# obdlogger_v0_2.net
KiCad netlist of a schematic drawn in EAGLE
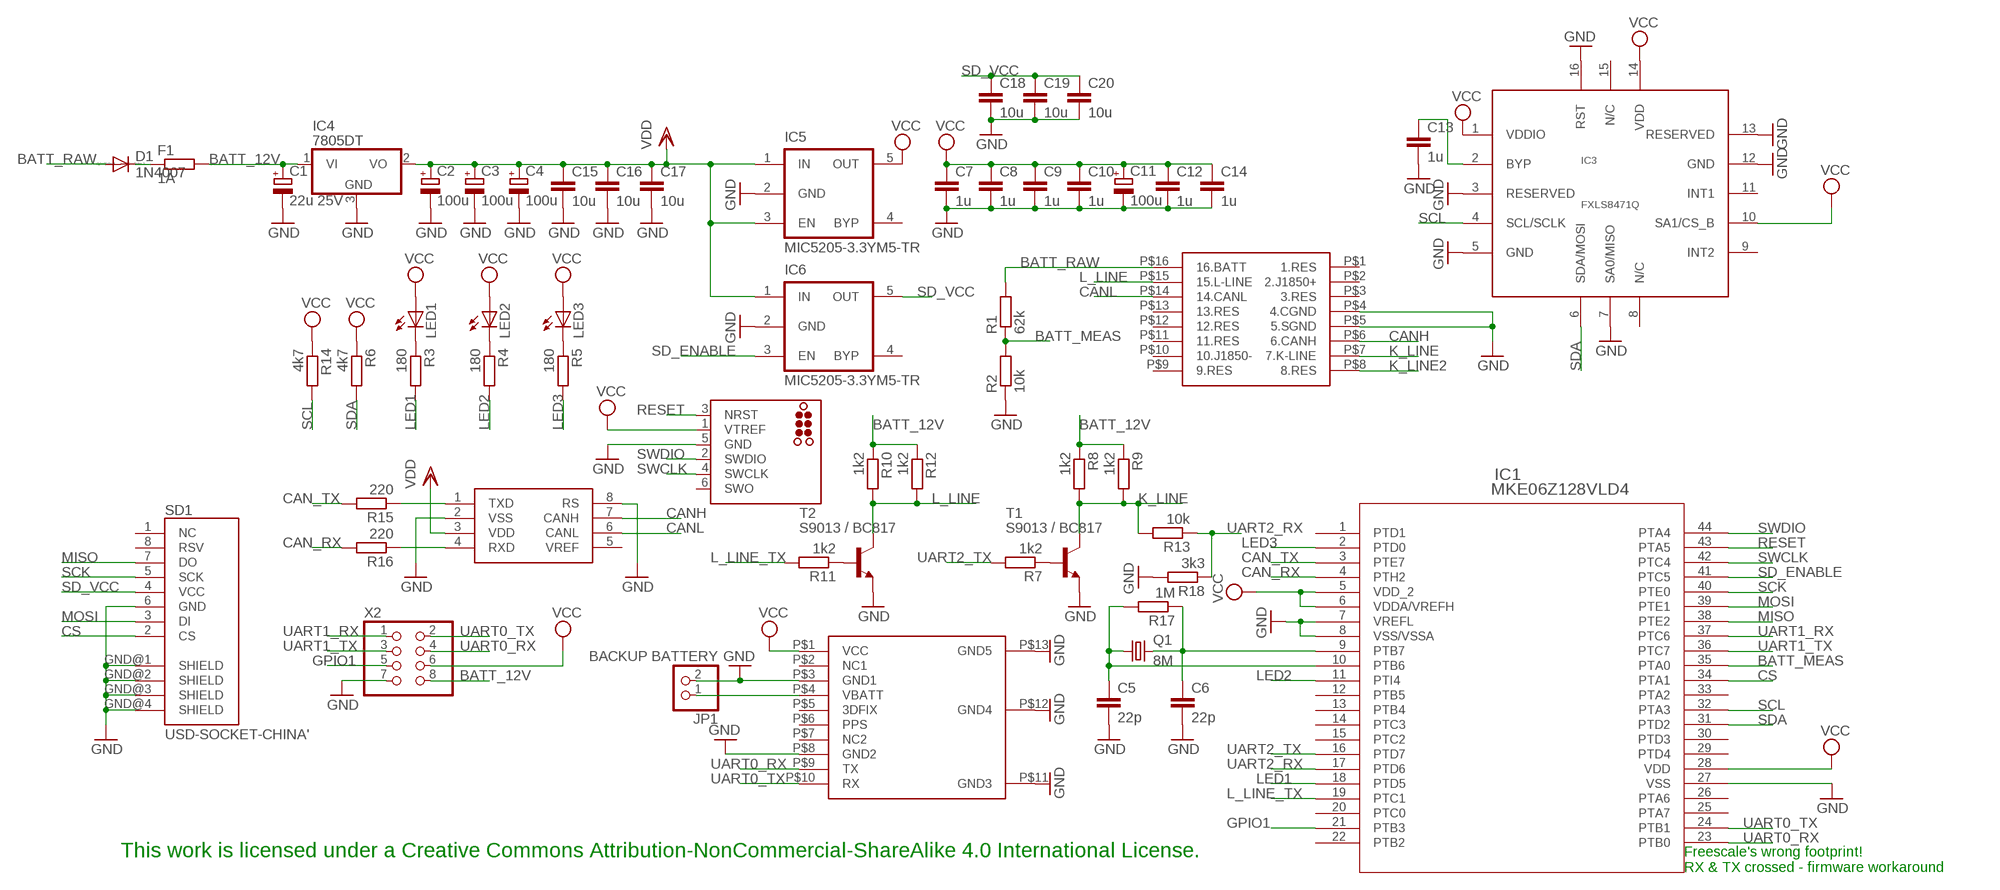
[diagram p0: schematic, sheet 1]

(export (version "E")
  (design (tool "Eeschema 10.0.6"))
  (components
    (comp (ref "C1")
      (value "22u 25V")
      (footprint "eagle-import:SMC_C")
      (libsource (lib "eagle-import") (part "CPOL-EUSMCC"))
    )
    (comp (ref "C2")
      (value "100u")
      (footprint "eagle-import:SMC_B")
      (libsource (lib "eagle-import") (part "CPOL-EUSMCB"))
    )
    (comp (ref "C3")
      (value "100u")
      (footprint "eagle-import:SMC_B")
      (libsource (lib "eagle-import") (part "CPOL-EUSMCB"))
    )
    (comp (ref "C4")
      (value "100u")
      (footprint "eagle-import:SMC_B")
      (libsource (lib "eagle-import") (part "CPOL-EUSMCB"))
    )
    (comp (ref "C5")
      (value "22p")
      (footprint "eagle-import:C0603K")
      (libsource (lib "eagle-import") (part "C-EUC0603K"))
    )
    (comp (ref "C6")
      (value "22p")
      (footprint "eagle-import:C0603K")
      (libsource (lib "eagle-import") (part "C-EUC0603K"))
    )
    (comp (ref "C7")
      (value "1u")
      (footprint "eagle-import:C0603K")
      (libsource (lib "eagle-import") (part "C-EUC0603K"))
    )
    (comp (ref "C8")
      (value "1u")
      (footprint "eagle-import:C0603K")
      (libsource (lib "eagle-import") (part "C-EUC0603K"))
    )
    (comp (ref "C9")
      (value "1u")
      (footprint "eagle-import:C0603K")
      (libsource (lib "eagle-import") (part "C-EUC0603K"))
    )
    (comp (ref "C10")
      (value "1u")
      (footprint "eagle-import:C0603K")
      (libsource (lib "eagle-import") (part "C-EUC0603K"))
    )
    (comp (ref "C11")
      (value "100u")
      (footprint "eagle-import:SMC_B")
      (libsource (lib "eagle-import") (part "CPOL-EUSMCB"))
    )
    (comp (ref "C12")
      (value "1u")
      (footprint "eagle-import:C0603K")
      (libsource (lib "eagle-import") (part "C-EUC0603K"))
    )
    (comp (ref "C13")
      (value "1u")
      (footprint "eagle-import:C0603K")
      (libsource (lib "eagle-import") (part "C-EUC0603K"))
    )
    (comp (ref "C14")
      (value "1u")
      (footprint "eagle-import:C0603K")
      (libsource (lib "eagle-import") (part "C-EUC0603K"))
    )
    (comp (ref "C15")
      (value "10u")
      (footprint "eagle-import:C0603K")
      (libsource (lib "eagle-import") (part "C-EUC0603K"))
    )
    (comp (ref "C16")
      (value "10u")
      (footprint "eagle-import:C0603K")
      (libsource (lib "eagle-import") (part "C-EUC0603K"))
    )
    (comp (ref "C17")
      (value "10u")
      (footprint "eagle-import:C0603K")
      (libsource (lib "eagle-import") (part "C-EUC0603K"))
    )
    (comp (ref "C18")
      (value "10u")
      (footprint "eagle-import:C0603K")
      (libsource (lib "eagle-import") (part "C-EUC0603K"))
    )
    (comp (ref "C19")
      (value "10u")
      (footprint "eagle-import:C0603K")
      (libsource (lib "eagle-import") (part "C-EUC0603K"))
    )
    (comp (ref "C20")
      (value "10u")
      (footprint "eagle-import:C0603K")
      (libsource (lib "eagle-import") (part "C-EUC0603K"))
    )
    (comp (ref "D1")
      (value "1N4007")
      (footprint "eagle-import:C1702-05")
      (libsource (lib "eagle-import") (part "DIODE-C1702-05"))
    )
    (comp (ref "F1")
      (value "1A")
      (footprint "eagle-import:R1206")
      (libsource (lib "eagle-import") (part "resistor_348_R-EU_R1206"))
    )
    (comp (ref "IC1")
      (value "MKE06Z128VLD4")
      (footprint "eagle-import:LQFP-44_10X10X1.4")
      (fields (field (name "MANUFACTURER_PART_NUMBER") "mke06z128vld4"))
      (libsource (lib "eagle-import") (part "MKE06Z128VLD4"))
    )
    (comp (ref "IC2")
      (value "MCP2561")
      (footprint "eagle-import:SO08")
      (libsource (lib "eagle-import") (part "MCP2551"))
    )
    (comp (ref "IC3")
      (value "FXLS8471Q")
      (footprint "eagle-import:16QFN-5_3")
      (libsource (lib "eagle-import") (part "FXLS8471Q"))
    )
    (comp (ref "IC4")
      (value "7805DT")
      (footprint "eagle-import:TO252")
      (libsource (lib "eagle-import") (part "78DT05"))
    )
    (comp (ref "IC5")
      (value "MIC5205-3.3YM5-TR")
      (footprint "eagle-import:SOT-23-5")
      (libsource (lib "eagle-import") (part "MIC5205"))
    )
    (comp (ref "IC6")
      (value "MIC5205-3.3YM5-TR")
      (footprint "eagle-import:SOT-23-5")
      (libsource (lib "eagle-import") (part "MIC5205"))
    )
    (comp (ref "JP1")
      (value "BACKUP BATTERY")
      (footprint "eagle-import:1X02")
      (libsource (lib "eagle-import") (part "PINHD-1X2"))
    )
    (comp (ref "LED1")
      (value "LED3MM")
      (footprint "eagle-import:LED3MM")
      (libsource (lib "eagle-import") (part "LED3MM"))
    )
    (comp (ref "LED2")
      (value "LED3MM")
      (footprint "eagle-import:LED3MM")
      (libsource (lib "eagle-import") (part "LED3MM"))
    )
    (comp (ref "LED3")
      (value "LED3MM")
      (footprint "eagle-import:LED3MM")
      (libsource (lib "eagle-import") (part "LED3MM"))
    )
    (comp (ref "Q1")
      (value "8M")
      (footprint "eagle-import:HC49UP")
      (libsource (lib "eagle-import") (part "CRYSTALHC49UP"))
    )
    (comp (ref "R1")
      (value "62k")
      (footprint "eagle-import:R0603")
      (libsource (lib "eagle-import") (part "R-EU_R0603"))
    )
    (comp (ref "R2")
      (value "10k")
      (footprint "eagle-import:R0603")
      (libsource (lib "eagle-import") (part "R-EU_R0603"))
    )
    (comp (ref "R3")
      (value "180")
      (footprint "eagle-import:R0603")
      (libsource (lib "eagle-import") (part "R-EU_R0603"))
    )
    (comp (ref "R4")
      (value "180")
      (footprint "eagle-import:R0603")
      (libsource (lib "eagle-import") (part "R-EU_R0603"))
    )
    (comp (ref "R5")
      (value "180")
      (footprint "eagle-import:R0603")
      (libsource (lib "eagle-import") (part "R-EU_R0603"))
    )
    (comp (ref "R6")
      (value "4k7")
      (footprint "eagle-import:R0603")
      (libsource (lib "eagle-import") (part "R-EU_R0603"))
    )
    (comp (ref "R7")
      (value "1k2")
      (footprint "eagle-import:R0603")
      (libsource (lib "eagle-import") (part "R-EU_R0603"))
    )
    (comp (ref "R8")
      (value "1k2")
      (footprint "eagle-import:M1206")
      (libsource (lib "eagle-import") (part "R-EU_M1206"))
    )
    (comp (ref "R9")
      (value "1k2")
      (footprint "eagle-import:M1206")
      (libsource (lib "eagle-import") (part "R-EU_M1206"))
    )
    (comp (ref "R10")
      (value "1k2")
      (footprint "eagle-import:M1206")
      (libsource (lib "eagle-import") (part "R-EU_M1206"))
    )
    (comp (ref "R11")
      (value "1k2")
      (footprint "eagle-import:R0603")
      (libsource (lib "eagle-import") (part "R-EU_R0603"))
    )
    (comp (ref "R12")
      (value "1k2")
      (footprint "eagle-import:M1206")
      (libsource (lib "eagle-import") (part "R-EU_M1206"))
    )
    (comp (ref "R13")
      (value "10k")
      (footprint "eagle-import:R0603")
      (libsource (lib "eagle-import") (part "R-EU_R0603"))
    )
    (comp (ref "R14")
      (value "4k7")
      (footprint "eagle-import:R0603")
      (libsource (lib "eagle-import") (part "R-EU_R0603"))
    )
    (comp (ref "R15")
      (value "220")
      (footprint "eagle-import:R0603")
      (libsource (lib "eagle-import") (part "R-EU_R0603"))
    )
    (comp (ref "R16")
      (value "220")
      (footprint "eagle-import:R0603")
      (libsource (lib "eagle-import") (part "R-EU_R0603"))
    )
    (comp (ref "R17")
      (value "1M")
      (footprint "eagle-import:R0603")
      (libsource (lib "eagle-import") (part "R-EU_R0603"))
    )
    (comp (ref "R18")
      (value "3k3")
      (footprint "eagle-import:R0603")
      (libsource (lib "eagle-import") (part "R-EU_R0603"))
    )
    (comp (ref "SD1")
      (value "USD-SOCKET-CHINA'")
      (footprint "eagle-import:USD-SOCKET-PP")
      (libsource (lib "eagle-import") (part "USD-SOCKET-CHINA'"))
    )
    (comp (ref "T1")
      (value "S9013 / BC817")
      (footprint "eagle-import:SOT23-BEC")
      (libsource (lib "eagle-import") (part "-NPN-SOT23-BECBC817-16"))
    )
    (comp (ref "T2")
      (value "S9013 / BC817")
      (footprint "eagle-import:SOT23-BEC")
      (libsource (lib "eagle-import") (part "-NPN-SOT23-BECBC817-16"))
    )
    (comp (ref "U$2")
      (value "SWD-NEEDLE")
      (footprint "eagle-import:TC2030-MCP")
      (libsource (lib "eagle-import") (part "SWD-NEEDLE"))
    )
    (comp (ref "U$4")
      (value "PA6C")
      (footprint "eagle-import:PA6C")
      (libsource (lib "eagle-import") (part "PA6C"))
    )
    (comp (ref "X1")
      (value "OBD2-RIGHT-ANGLEPROPER")
      (footprint "eagle-import:OBD2-RIGHT-ANGLE-PCB-PROPER")
      (libsource (lib "eagle-import") (part "OBD2-RIGHT-ANGLEPROPER"))
    )
    (comp (ref "X2")
      (value "PINHD-2X4")
      (footprint "eagle-import:2X04")
      (libsource (lib "eagle-import") (part "PINHD-2X4"))
    )
  )
  (nets
    (net (code "1") (name "/BATT_12V") (class "Default")
      (node (ref "C1") (pin "+") (pinfunction "+_+") (pintype "passive"))
      (node (ref "F1") (pin "2") (pinfunction "2_2") (pintype "passive"))
      (node (ref "IC4") (pin "1") (pinfunction "VI_1") (pintype "input"))
      (node (ref "R10") (pin "1") (pinfunction "1_1") (pintype "passive"))
      (node (ref "R12") (pin "1") (pinfunction "1_1") (pintype "passive"))
      (node (ref "R8") (pin "1") (pinfunction "1_1") (pintype "passive"))
      (node (ref "R9") (pin "1") (pinfunction "1_1") (pintype "passive"))
      (node (ref "X2") (pin "8") (pinfunction "8_8") (pintype "passive"))
    )
    (net (code "2") (name "/BATT_MEAS") (class "Default")
      (node (ref "IC1") (pin "35") (pinfunction "PTA0_35") (pintype "bidirectional"))
      (node (ref "R1") (pin "1") (pinfunction "1_1") (pintype "passive"))
      (node (ref "R2") (pin "2") (pinfunction "2_2") (pintype "passive"))
    )
    (net (code "3") (name "/BATT_RAW") (class "Default")
      (node (ref "D1") (pin "A") (pinfunction "A_A") (pintype "passive"))
      (node (ref "R1") (pin "2") (pinfunction "2_2") (pintype "passive"))
      (node (ref "X1") (pin "P$16") (pinfunction "16.BATT_P$16") (pintype "bidirectional"))
    )
    (net (code "4") (name "/CANH") (class "Default")
      (node (ref "IC2") (pin "7") (pinfunction "CANH_7") (pintype "bidirectional"))
      (node (ref "X1") (pin "P$6") (pinfunction "6.CANH_P$6") (pintype "bidirectional"))
    )
    (net (code "5") (name "/CANL") (class "Default")
      (node (ref "IC2") (pin "6") (pinfunction "CANL_6") (pintype "bidirectional"))
      (node (ref "X1") (pin "P$14") (pinfunction "14.CANL_P$14") (pintype "bidirectional"))
    )
    (net (code "6") (name "/CAN_RX") (class "Default")
      (node (ref "IC1") (pin "4") (pinfunction "PTH2_4") (pintype "bidirectional"))
      (node (ref "R16") (pin "2") (pinfunction "2_2") (pintype "passive"))
    )
    (net (code "7") (name "/CAN_TX") (class "Default")
      (node (ref "IC1") (pin "3") (pinfunction "PTE7_3") (pintype "bidirectional"))
      (node (ref "R15") (pin "2") (pinfunction "2_2") (pintype "passive"))
    )
    (net (code "8") (name "/CS") (class "Default")
      (node (ref "IC1") (pin "34") (pinfunction "PTA1_34") (pintype "bidirectional"))
      (node (ref "SD1") (pin "2") (pinfunction "CS_2") (pintype "bidirectional"))
    )
    (net (code "9") (name "/GPIO1") (class "Default")
      (node (ref "IC1") (pin "21") (pinfunction "PTB3_21") (pintype "bidirectional"))
      (node (ref "X2") (pin "5") (pinfunction "5_5") (pintype "passive"))
    )
    (net (code "10") (name "/K_LINE") (class "Default")
      (node (ref "R13") (pin "2") (pinfunction "2_2") (pintype "passive"))
      (node (ref "R8") (pin "2") (pinfunction "2_2") (pintype "passive"))
      (node (ref "R9") (pin "2") (pinfunction "2_2") (pintype "passive"))
      (node (ref "T1") (pin "C") (pinfunction "C_C") (pintype "passive"))
      (node (ref "X1") (pin "P$7") (pinfunction "7.K-LINE_P$7") (pintype "bidirectional"))
    )
    (net (code "11") (name "/K_LINE2") (class "Default")
      (node (ref "X1") (pin "P$8") (pinfunction "8.RES_P$8") (pintype "bidirectional"))
    )
    (net (code "12") (name "/LED1") (class "Default")
      (node (ref "IC1") (pin "18") (pinfunction "PTD5_18") (pintype "bidirectional"))
      (node (ref "R3") (pin "2") (pinfunction "2_2") (pintype "passive"))
    )
    (net (code "13") (name "/LED2") (class "Default")
      (node (ref "IC1") (pin "11") (pinfunction "PTI4_11") (pintype "bidirectional"))
      (node (ref "R4") (pin "2") (pinfunction "2_2") (pintype "passive"))
    )
    (net (code "14") (name "/LED3") (class "Default")
      (node (ref "IC1") (pin "2") (pinfunction "PTD0_2") (pintype "bidirectional"))
      (node (ref "R5") (pin "2") (pinfunction "2_2") (pintype "passive"))
    )
    (net (code "15") (name "/L_LINE") (class "Default")
      (node (ref "R10") (pin "2") (pinfunction "2_2") (pintype "passive"))
      (node (ref "R12") (pin "2") (pinfunction "2_2") (pintype "passive"))
      (node (ref "T2") (pin "C") (pinfunction "C_C") (pintype "passive"))
      (node (ref "X1") (pin "P$15") (pinfunction "15.L-LINE_P$15") (pintype "bidirectional"))
    )
    (net (code "16") (name "/L_LINE_TX") (class "Default")
      (node (ref "IC1") (pin "19") (pinfunction "PTC1_19") (pintype "bidirectional"))
      (node (ref "R11") (pin "2") (pinfunction "2_2") (pintype "passive"))
    )
    (net (code "17") (name "/MISO") (class "Default")
      (node (ref "IC1") (pin "38") (pinfunction "PTE2_38") (pintype "bidirectional"))
      (node (ref "SD1") (pin "7") (pinfunction "DO_7") (pintype "bidirectional"))
    )
    (net (code "18") (name "/MOSI") (class "Default")
      (node (ref "IC1") (pin "39") (pinfunction "PTE1_39") (pintype "bidirectional"))
      (node (ref "SD1") (pin "3") (pinfunction "DI_3") (pintype "bidirectional"))
    )
    (net (code "19") (name "/RESET") (class "Default")
      (node (ref "IC1") (pin "43") (pinfunction "PTA5_43") (pintype "bidirectional"))
      (node (ref "U$2") (pin "3") (pinfunction "NRST_3") (pintype "passive"))
    )
    (net (code "20") (name "/SCK") (class "Default")
      (node (ref "IC1") (pin "40") (pinfunction "PTE0_40") (pintype "bidirectional"))
      (node (ref "SD1") (pin "5") (pinfunction "SCK_5") (pintype "bidirectional"))
    )
    (net (code "21") (name "/SCL") (class "Default")
      (node (ref "IC1") (pin "32") (pinfunction "PTA3_32") (pintype "bidirectional"))
      (node (ref "IC3") (pin "4") (pinfunction "SCL/SCLK_4") (pintype "bidirectional"))
      (node (ref "R14") (pin "2") (pinfunction "2_2") (pintype "passive"))
    )
    (net (code "22") (name "/SDA") (class "Default")
      (node (ref "IC1") (pin "31") (pinfunction "PTD2_31") (pintype "bidirectional"))
      (node (ref "IC3") (pin "6") (pinfunction "SDA/MOSI_6") (pintype "bidirectional"))
      (node (ref "R6") (pin "2") (pinfunction "2_2") (pintype "passive"))
    )
    (net (code "23") (name "/SD_ENABLE") (class "Default")
      (node (ref "IC1") (pin "41") (pinfunction "PTC5_41") (pintype "bidirectional"))
      (node (ref "IC6") (pin "3") (pinfunction "EN_3") (pintype "bidirectional"))
    )
    (net (code "24") (name "/SD_VCC") (class "Default")
      (node (ref "C18") (pin "1") (pinfunction "1_1") (pintype "passive"))
      (node (ref "C19") (pin "1") (pinfunction "1_1") (pintype "passive"))
      (node (ref "C20") (pin "1") (pinfunction "1_1") (pintype "passive"))
      (node (ref "IC6") (pin "5") (pinfunction "OUT_5") (pintype "bidirectional"))
      (node (ref "SD1") (pin "4") (pinfunction "VCC_4") (pintype "bidirectional"))
    )
    (net (code "25") (name "/SWCLK") (class "Default")
      (node (ref "IC1") (pin "42") (pinfunction "PTC4_42") (pintype "bidirectional"))
      (node (ref "U$2") (pin "4") (pinfunction "SWCLK_4") (pintype "output"))
    )
    (net (code "26") (name "/SWDIO") (class "Default")
      (node (ref "IC1") (pin "44") (pinfunction "PTA4_44") (pintype "bidirectional"))
      (node (ref "U$2") (pin "2") (pinfunction "SWDIO_2") (pintype "bidirectional"))
    )
    (net (code "27") (name "/UART0_RX") (class "Default")
      (node (ref "IC1") (pin "23") (pinfunction "PTB0_23") (pintype "bidirectional"))
      (node (ref "U$4") (pin "P$9") (pinfunction "TX_P$9") (pintype "bidirectional"))
      (node (ref "X2") (pin "4") (pinfunction "4_4") (pintype "passive"))
    )
    (net (code "28") (name "/UART0_TX") (class "Default")
      (node (ref "IC1") (pin "24") (pinfunction "PTB1_24") (pintype "bidirectional"))
      (node (ref "U$4") (pin "P$10") (pinfunction "RX_P$10") (pintype "bidirectional"))
      (node (ref "X2") (pin "2") (pinfunction "2_2") (pintype "passive"))
    )
    (net (code "29") (name "/UART1_RX") (class "Default")
      (node (ref "IC1") (pin "37") (pinfunction "PTC6_37") (pintype "bidirectional"))
      (node (ref "X2") (pin "1") (pinfunction "1_1") (pintype "passive"))
    )
    (net (code "30") (name "/UART1_TX") (class "Default")
      (node (ref "IC1") (pin "36") (pinfunction "PTC7_36") (pintype "bidirectional"))
      (node (ref "X2") (pin "3") (pinfunction "3_3") (pintype "passive"))
    )
    (net (code "31") (name "/UART2_RX") (class "Default")
      (node (ref "IC1") (pin "17") (pinfunction "PTD6_17") (pintype "bidirectional"))
      (node (ref "R13") (pin "1") (pinfunction "1_1") (pintype "passive"))
      (node (ref "R18") (pin "1") (pinfunction "1_1") (pintype "passive"))
    )
    (net (code "32") (name "/UART2_TX") (class "Default")
      (node (ref "IC1") (pin "16") (pinfunction "PTD7_16") (pintype "bidirectional"))
      (node (ref "R7") (pin "2") (pinfunction "2_2") (pintype "passive"))
    )
    (net (code "33") (name "GND") (class "Default")
      (node (ref "C1") (pin "-") (pinfunction "-_-") (pintype "passive"))
      (node (ref "C10") (pin "2") (pinfunction "2_2") (pintype "passive"))
      (node (ref "C11") (pin "-") (pinfunction "-_-") (pintype "passive"))
      (node (ref "C12") (pin "2") (pinfunction "2_2") (pintype "passive"))
      (node (ref "C13") (pin "2") (pinfunction "2_2") (pintype "passive"))
      (node (ref "C14") (pin "2") (pinfunction "2_2") (pintype "passive"))
      (node (ref "C15") (pin "2") (pinfunction "2_2") (pintype "passive"))
      (node (ref "C16") (pin "2") (pinfunction "2_2") (pintype "passive"))
      (node (ref "C17") (pin "2") (pinfunction "2_2") (pintype "passive"))
      (node (ref "C18") (pin "2") (pinfunction "2_2") (pintype "passive"))
      (node (ref "C19") (pin "2") (pinfunction "2_2") (pintype "passive"))
      (node (ref "C2") (pin "-") (pinfunction "-_-") (pintype "passive"))
      (node (ref "C20") (pin "2") (pinfunction "2_2") (pintype "passive"))
      (node (ref "C3") (pin "-") (pinfunction "-_-") (pintype "passive"))
      (node (ref "C4") (pin "-") (pinfunction "-_-") (pintype "passive"))
      (node (ref "C5") (pin "2") (pinfunction "2_2") (pintype "passive"))
      (node (ref "C6") (pin "2") (pinfunction "2_2") (pintype "passive"))
      (node (ref "C7") (pin "2") (pinfunction "2_2") (pintype "passive"))
      (node (ref "C8") (pin "2") (pinfunction "2_2") (pintype "passive"))
      (node (ref "C9") (pin "2") (pinfunction "2_2") (pintype "passive"))
      (node (ref "IC1") (pin "27") (pinfunction "VSS_27") (pintype "power_in"))
      (node (ref "IC1") (pin "7") (pinfunction "VREFL_7") (pintype "power_in"))
      (node (ref "IC1") (pin "8") (pinfunction "VSS/VSSA_8") (pintype "power_in"))
      (node (ref "IC2") (pin "2") (pinfunction "VSS_2") (pintype "bidirectional"))
      (node (ref "IC2") (pin "8") (pinfunction "RS_8") (pintype "bidirectional"))
      (node (ref "IC3") (pin "12") (pinfunction "GND_12") (pintype "bidirectional"))
      (node (ref "IC3") (pin "13") (pinfunction "RESERVED_13") (pintype "bidirectional"))
      (node (ref "IC3") (pin "16") (pinfunction "RST_16") (pintype "bidirectional"))
      (node (ref "IC3") (pin "3") (pinfunction "RESERVED_3") (pintype "bidirectional"))
      (node (ref "IC3") (pin "5") (pinfunction "GND_5") (pintype "bidirectional"))
      (node (ref "IC3") (pin "7") (pinfunction "SA0/MISO_7") (pintype "bidirectional"))
      (node (ref "IC4") (pin "3") (pinfunction "GND_3") (pintype "passive"))
      (node (ref "IC5") (pin "2") (pinfunction "GND_2") (pintype "bidirectional"))
      (node (ref "IC6") (pin "2") (pinfunction "GND_2") (pintype "bidirectional"))
      (node (ref "JP1") (pin "2") (pinfunction "2_2") (pintype "passive"))
      (node (ref "R18") (pin "2") (pinfunction "2_2") (pintype "passive"))
      (node (ref "R2") (pin "1") (pinfunction "1_1") (pintype "passive"))
      (node (ref "SD1") (pin "6") (pinfunction "GND_6") (pintype "bidirectional"))
      (node (ref "SD1") (pin "GND@1") (pinfunction "SHIELD_GND@1") (pintype "bidirectional"))
      (node (ref "SD1") (pin "GND@2") (pinfunction "SHIELD_GND@2") (pintype "bidirectional"))
      (node (ref "SD1") (pin "GND@3") (pinfunction "SHIELD_GND@3") (pintype "bidirectional"))
      (node (ref "SD1") (pin "GND@4") (pinfunction "SHIELD_GND@4") (pintype "bidirectional"))
      (node (ref "T1") (pin "E") (pinfunction "E_E") (pintype "passive"))
      (node (ref "T2") (pin "E") (pinfunction "E_E") (pintype "passive"))
      (node (ref "U$2") (pin "5") (pinfunction "GND_5") (pintype "power_in"))
      (node (ref "U$4") (pin "P$11") (pinfunction "GND3_P$11") (pintype "bidirectional"))
      (node (ref "U$4") (pin "P$12") (pinfunction "GND4_P$12") (pintype "bidirectional"))
      (node (ref "U$4") (pin "P$13") (pinfunction "GND5_P$13") (pintype "bidirectional"))
      (node (ref "U$4") (pin "P$3") (pinfunction "GND1_P$3") (pintype "bidirectional"))
      (node (ref "U$4") (pin "P$8") (pinfunction "GND2_P$8") (pintype "bidirectional"))
      (node (ref "X1") (pin "P$4") (pinfunction "4.CGND_P$4") (pintype "bidirectional"))
      (node (ref "X1") (pin "P$5") (pinfunction "5.SGND_P$5") (pintype "bidirectional"))
      (node (ref "X2") (pin "7") (pinfunction "7_7") (pintype "passive"))
    )
    (net (code "34") (name "Net-(D1-PadC)") (class "Default")
      (node (ref "D1") (pin "C") (pinfunction "C_C") (pintype "passive"))
      (node (ref "F1") (pin "1") (pinfunction "1_1") (pintype "passive"))
    )
    (net (code "35") (name "Net-(IC1-PTB6)") (class "Default")
      (node (ref "C5") (pin "1") (pinfunction "1_1") (pintype "passive"))
      (node (ref "IC1") (pin "10") (pinfunction "PTB6_10") (pintype "bidirectional"))
      (node (ref "Q1") (pin "1") (pinfunction "1_1") (pintype "passive"))
      (node (ref "R17") (pin "2") (pinfunction "2_2") (pintype "passive"))
    )
    (net (code "36") (name "Net-(IC1-PTB7)") (class "Default")
      (node (ref "C6") (pin "1") (pinfunction "1_1") (pintype "passive"))
      (node (ref "IC1") (pin "9") (pinfunction "PTB7_9") (pintype "bidirectional"))
      (node (ref "Q1") (pin "2") (pinfunction "2_2") (pintype "passive"))
      (node (ref "R17") (pin "1") (pinfunction "1_1") (pintype "passive"))
    )
    (net (code "37") (name "Net-(IC2-RXD)") (class "Default")
      (node (ref "IC2") (pin "4") (pinfunction "RXD_4") (pintype "bidirectional"))
      (node (ref "R16") (pin "1") (pinfunction "1_1") (pintype "passive"))
    )
    (net (code "38") (name "Net-(IC2-TXD)") (class "Default")
      (node (ref "IC2") (pin "1") (pinfunction "TXD_1") (pintype "bidirectional"))
      (node (ref "R15") (pin "1") (pinfunction "1_1") (pintype "passive"))
    )
    (net (code "39") (name "Net-(IC3-BYP)") (class "Default")
      (node (ref "C13") (pin "1") (pinfunction "1_1") (pintype "passive"))
      (node (ref "IC3") (pin "2") (pinfunction "BYP_2") (pintype "bidirectional"))
    )
    (net (code "40") (name "Net-(LED1-C)") (class "Default")
      (node (ref "LED1") (pin "K") (pinfunction "C_K") (pintype "passive"))
      (node (ref "R3") (pin "1") (pinfunction "1_1") (pintype "passive"))
    )
    (net (code "41") (name "Net-(LED2-C)") (class "Default")
      (node (ref "LED2") (pin "K") (pinfunction "C_K") (pintype "passive"))
      (node (ref "R4") (pin "1") (pinfunction "1_1") (pintype "passive"))
    )
    (net (code "42") (name "Net-(LED3-C)") (class "Default")
      (node (ref "LED3") (pin "K") (pinfunction "C_K") (pintype "passive"))
      (node (ref "R5") (pin "1") (pinfunction "1_1") (pintype "passive"))
    )
    (net (code "43") (name "Net-(R7-Pad1)") (class "Default")
      (node (ref "R7") (pin "1") (pinfunction "1_1") (pintype "passive"))
      (node (ref "T1") (pin "B") (pinfunction "B_B") (pintype "passive"))
    )
    (net (code "44") (name "Net-(R11-Pad1)") (class "Default")
      (node (ref "R11") (pin "1") (pinfunction "1_1") (pintype "passive"))
      (node (ref "T2") (pin "B") (pinfunction "B_B") (pintype "passive"))
    )
    (net (code "45") (name "Net-(U$4-VBATT)") (class "Default")
      (node (ref "JP1") (pin "1") (pinfunction "1_1") (pintype "passive"))
      (node (ref "U$4") (pin "P$4") (pinfunction "VBATT_P$4") (pintype "bidirectional"))
    )
    (net (code "46") (name "VCC") (class "Default")
      (node (ref "C10") (pin "1") (pinfunction "1_1") (pintype "passive"))
      (node (ref "C11") (pin "+") (pinfunction "+_+") (pintype "passive"))
      (node (ref "C12") (pin "1") (pinfunction "1_1") (pintype "passive"))
      (node (ref "C14") (pin "1") (pinfunction "1_1") (pintype "passive"))
      (node (ref "C7") (pin "1") (pinfunction "1_1") (pintype "passive"))
      (node (ref "C8") (pin "1") (pinfunction "1_1") (pintype "passive"))
      (node (ref "C9") (pin "1") (pinfunction "1_1") (pintype "passive"))
      (node (ref "IC1") (pin "28") (pinfunction "VDD_28") (pintype "power_in"))
      (node (ref "IC1") (pin "5") (pinfunction "VDD_2_5") (pintype "power_in"))
      (node (ref "IC1") (pin "6") (pinfunction "VDDA/VREFH_6") (pintype "power_in"))
      (node (ref "IC3") (pin "1") (pinfunction "VDDIO_1") (pintype "bidirectional"))
      (node (ref "IC3") (pin "10") (pinfunction "SA1/CS_B_10") (pintype "bidirectional"))
      (node (ref "IC3") (pin "14") (pinfunction "VDD_14") (pintype "bidirectional"))
      (node (ref "IC5") (pin "5") (pinfunction "OUT_5") (pintype "bidirectional"))
      (node (ref "LED1") (pin "A") (pinfunction "A_A") (pintype "passive"))
      (node (ref "LED2") (pin "A") (pinfunction "A_A") (pintype "passive"))
      (node (ref "LED3") (pin "A") (pinfunction "A_A") (pintype "passive"))
      (node (ref "R14") (pin "1") (pinfunction "1_1") (pintype "passive"))
      (node (ref "R6") (pin "1") (pinfunction "1_1") (pintype "passive"))
      (node (ref "U$2") (pin "1") (pinfunction "VTREF_1") (pintype "power_in"))
      (node (ref "U$4") (pin "P$1") (pinfunction "VCC_P$1") (pintype "bidirectional"))
      (node (ref "X2") (pin "6") (pinfunction "6_6") (pintype "passive"))
    )
    (net (code "47") (name "VDD") (class "Default")
      (node (ref "C15") (pin "1") (pinfunction "1_1") (pintype "passive"))
      (node (ref "C16") (pin "1") (pinfunction "1_1") (pintype "passive"))
      (node (ref "C17") (pin "1") (pinfunction "1_1") (pintype "passive"))
      (node (ref "C2") (pin "+") (pinfunction "+_+") (pintype "passive"))
      (node (ref "C3") (pin "+") (pinfunction "+_+") (pintype "passive"))
      (node (ref "C4") (pin "+") (pinfunction "+_+") (pintype "passive"))
      (node (ref "IC2") (pin "3") (pinfunction "VDD_3") (pintype "bidirectional"))
      (node (ref "IC4") (pin "2") (pinfunction "VO_2") (pintype "passive"))
      (node (ref "IC5") (pin "1") (pinfunction "IN_1") (pintype "bidirectional"))
      (node (ref "IC5") (pin "3") (pinfunction "EN_3") (pintype "bidirectional"))
      (node (ref "IC6") (pin "1") (pinfunction "IN_1") (pintype "bidirectional"))
    )
    (net (code "48") (name "unconnected-(IC1-PTA2-Pad33)") (class "Default")
      (node (ref "IC1") (pin "33") (pinfunction "PTA2_33") (pintype "bidirectional"))
    )
    (net (code "49") (name "unconnected-(IC1-PTA6-Pad26)") (class "Default")
      (node (ref "IC1") (pin "26") (pinfunction "PTA6_26") (pintype "bidirectional"))
    )
    (net (code "50") (name "unconnected-(IC1-PTA7-Pad25)") (class "Default")
      (node (ref "IC1") (pin "25") (pinfunction "PTA7_25") (pintype "bidirectional"))
    )
    (net (code "51") (name "unconnected-(IC1-PTB2-Pad22)") (class "Default")
      (node (ref "IC1") (pin "22") (pinfunction "PTB2_22") (pintype "bidirectional"))
    )
    (net (code "52") (name "unconnected-(IC1-PTB4-Pad13)") (class "Default")
      (node (ref "IC1") (pin "13") (pinfunction "PTB4_13") (pintype "bidirectional"))
    )
    (net (code "53") (name "unconnected-(IC1-PTB5-Pad12)") (class "Default")
      (node (ref "IC1") (pin "12") (pinfunction "PTB5_12") (pintype "bidirectional"))
    )
    (net (code "54") (name "unconnected-(IC1-PTC0-Pad20)") (class "Default")
      (node (ref "IC1") (pin "20") (pinfunction "PTC0_20") (pintype "bidirectional"))
    )
    (net (code "55") (name "unconnected-(IC1-PTC2-Pad15)") (class "Default")
      (node (ref "IC1") (pin "15") (pinfunction "PTC2_15") (pintype "bidirectional"))
    )
    (net (code "56") (name "unconnected-(IC1-PTC3-Pad14)") (class "Default")
      (node (ref "IC1") (pin "14") (pinfunction "PTC3_14") (pintype "bidirectional"))
    )
    (net (code "57") (name "unconnected-(IC1-PTD1-Pad1)") (class "Default")
      (node (ref "IC1") (pin "1") (pinfunction "PTD1_1") (pintype "bidirectional"))
    )
    (net (code "58") (name "unconnected-(IC1-PTD3-Pad30)") (class "Default")
      (node (ref "IC1") (pin "30") (pinfunction "PTD3_30") (pintype "bidirectional"))
    )
    (net (code "59") (name "unconnected-(IC1-PTD4-Pad29)") (class "Default")
      (node (ref "IC1") (pin "29") (pinfunction "PTD4_29") (pintype "bidirectional"))
    )
    (net (code "60") (name "unconnected-(IC2-VREF-Pad5)") (class "Default")
      (node (ref "IC2") (pin "5") (pinfunction "VREF_5") (pintype "bidirectional"))
    )
    (net (code "61") (name "unconnected-(IC3-INT1-Pad11)") (class "Default")
      (node (ref "IC3") (pin "11") (pinfunction "INT1_11") (pintype "bidirectional"))
    )
    (net (code "62") (name "unconnected-(IC3-INT2-Pad9)") (class "Default")
      (node (ref "IC3") (pin "9") (pinfunction "INT2_9") (pintype "bidirectional"))
    )
    (net (code "63") (name "unconnected-(IC3-N{slash}C-Pad8)") (class "Default")
      (node (ref "IC3") (pin "8") (pinfunction "N/C_8") (pintype "bidirectional"))
    )
    (net (code "64") (name "unconnected-(IC3-N{slash}C-Pad15)") (class "Default")
      (node (ref "IC3") (pin "15") (pinfunction "N/C_15") (pintype "bidirectional"))
    )
    (net (code "65") (name "unconnected-(IC5-BYP-Pad4)") (class "Default")
      (node (ref "IC5") (pin "4") (pinfunction "BYP_4") (pintype "bidirectional"))
    )
    (net (code "66") (name "unconnected-(IC6-BYP-Pad4)") (class "Default")
      (node (ref "IC6") (pin "4") (pinfunction "BYP_4") (pintype "bidirectional"))
    )
    (net (code "67") (name "unconnected-(SD1-NC-Pad1)") (class "Default")
      (node (ref "SD1") (pin "1") (pinfunction "NC_1") (pintype "bidirectional"))
    )
    (net (code "68") (name "unconnected-(SD1-RSV-Pad8)") (class "Default")
      (node (ref "SD1") (pin "8") (pinfunction "RSV_8") (pintype "bidirectional"))
    )
    (net (code "69") (name "unconnected-(U$2-SWO-Pad6)") (class "Default")
      (node (ref "U$2") (pin "6") (pinfunction "SWO_6") (pintype "bidirectional"))
    )
    (net (code "70") (name "unconnected-(U$4-3DFIX-PadP$5)") (class "Default")
      (node (ref "U$4") (pin "P$5") (pinfunction "3DFIX_P$5") (pintype "bidirectional"))
    )
    (net (code "71") (name "unconnected-(U$4-NC1-PadP$2)") (class "Default")
      (node (ref "U$4") (pin "P$2") (pinfunction "NC1_P$2") (pintype "bidirectional"))
    )
    (net (code "72") (name "unconnected-(U$4-NC2-PadP$7)") (class "Default")
      (node (ref "U$4") (pin "P$7") (pinfunction "NC2_P$7") (pintype "bidirectional"))
    )
    (net (code "73") (name "unconnected-(U$4-PPS-PadP$6)") (class "Default")
      (node (ref "U$4") (pin "P$6") (pinfunction "PPS_P$6") (pintype "bidirectional"))
    )
    (net (code "74") (name "unconnected-(X1-1.RES-PadP$1)") (class "Default")
      (node (ref "X1") (pin "P$1") (pinfunction "1.RES_P$1") (pintype "bidirectional"))
    )
    (net (code "75") (name "unconnected-(X1-2.J1850+-PadP$2)") (class "Default")
      (node (ref "X1") (pin "P$2") (pinfunction "2.J1850+_P$2") (pintype "bidirectional"))
    )
    (net (code "76") (name "unconnected-(X1-3.RES-PadP$3)") (class "Default")
      (node (ref "X1") (pin "P$3") (pinfunction "3.RES_P$3") (pintype "bidirectional"))
    )
    (net (code "77") (name "unconnected-(X1-9.RES-PadP$9)") (class "Default")
      (node (ref "X1") (pin "P$9") (pinfunction "9.RES_P$9") (pintype "bidirectional"))
    )
    (net (code "78") (name "unconnected-(X1-10.J1850--PadP$10)") (class "Default")
      (node (ref "X1") (pin "P$10") (pinfunction "10.J1850-_P$10") (pintype "bidirectional"))
    )
    (net (code "79") (name "unconnected-(X1-11.RES-PadP$11)") (class "Default")
      (node (ref "X1") (pin "P$11") (pinfunction "11.RES_P$11") (pintype "bidirectional"))
    )
    (net (code "80") (name "unconnected-(X1-12.RES-PadP$12)") (class "Default")
      (node (ref "X1") (pin "P$12") (pinfunction "12.RES_P$12") (pintype "bidirectional"))
    )
    (net (code "81") (name "unconnected-(X1-13.RES-PadP$13)") (class "Default")
      (node (ref "X1") (pin "P$13") (pinfunction "13.RES_P$13") (pintype "bidirectional"))
    )
  )
)
